# SCH_Flight-Computer_2024-07-14.net
KiCad netlist of a schematic drawn in EasyEDA
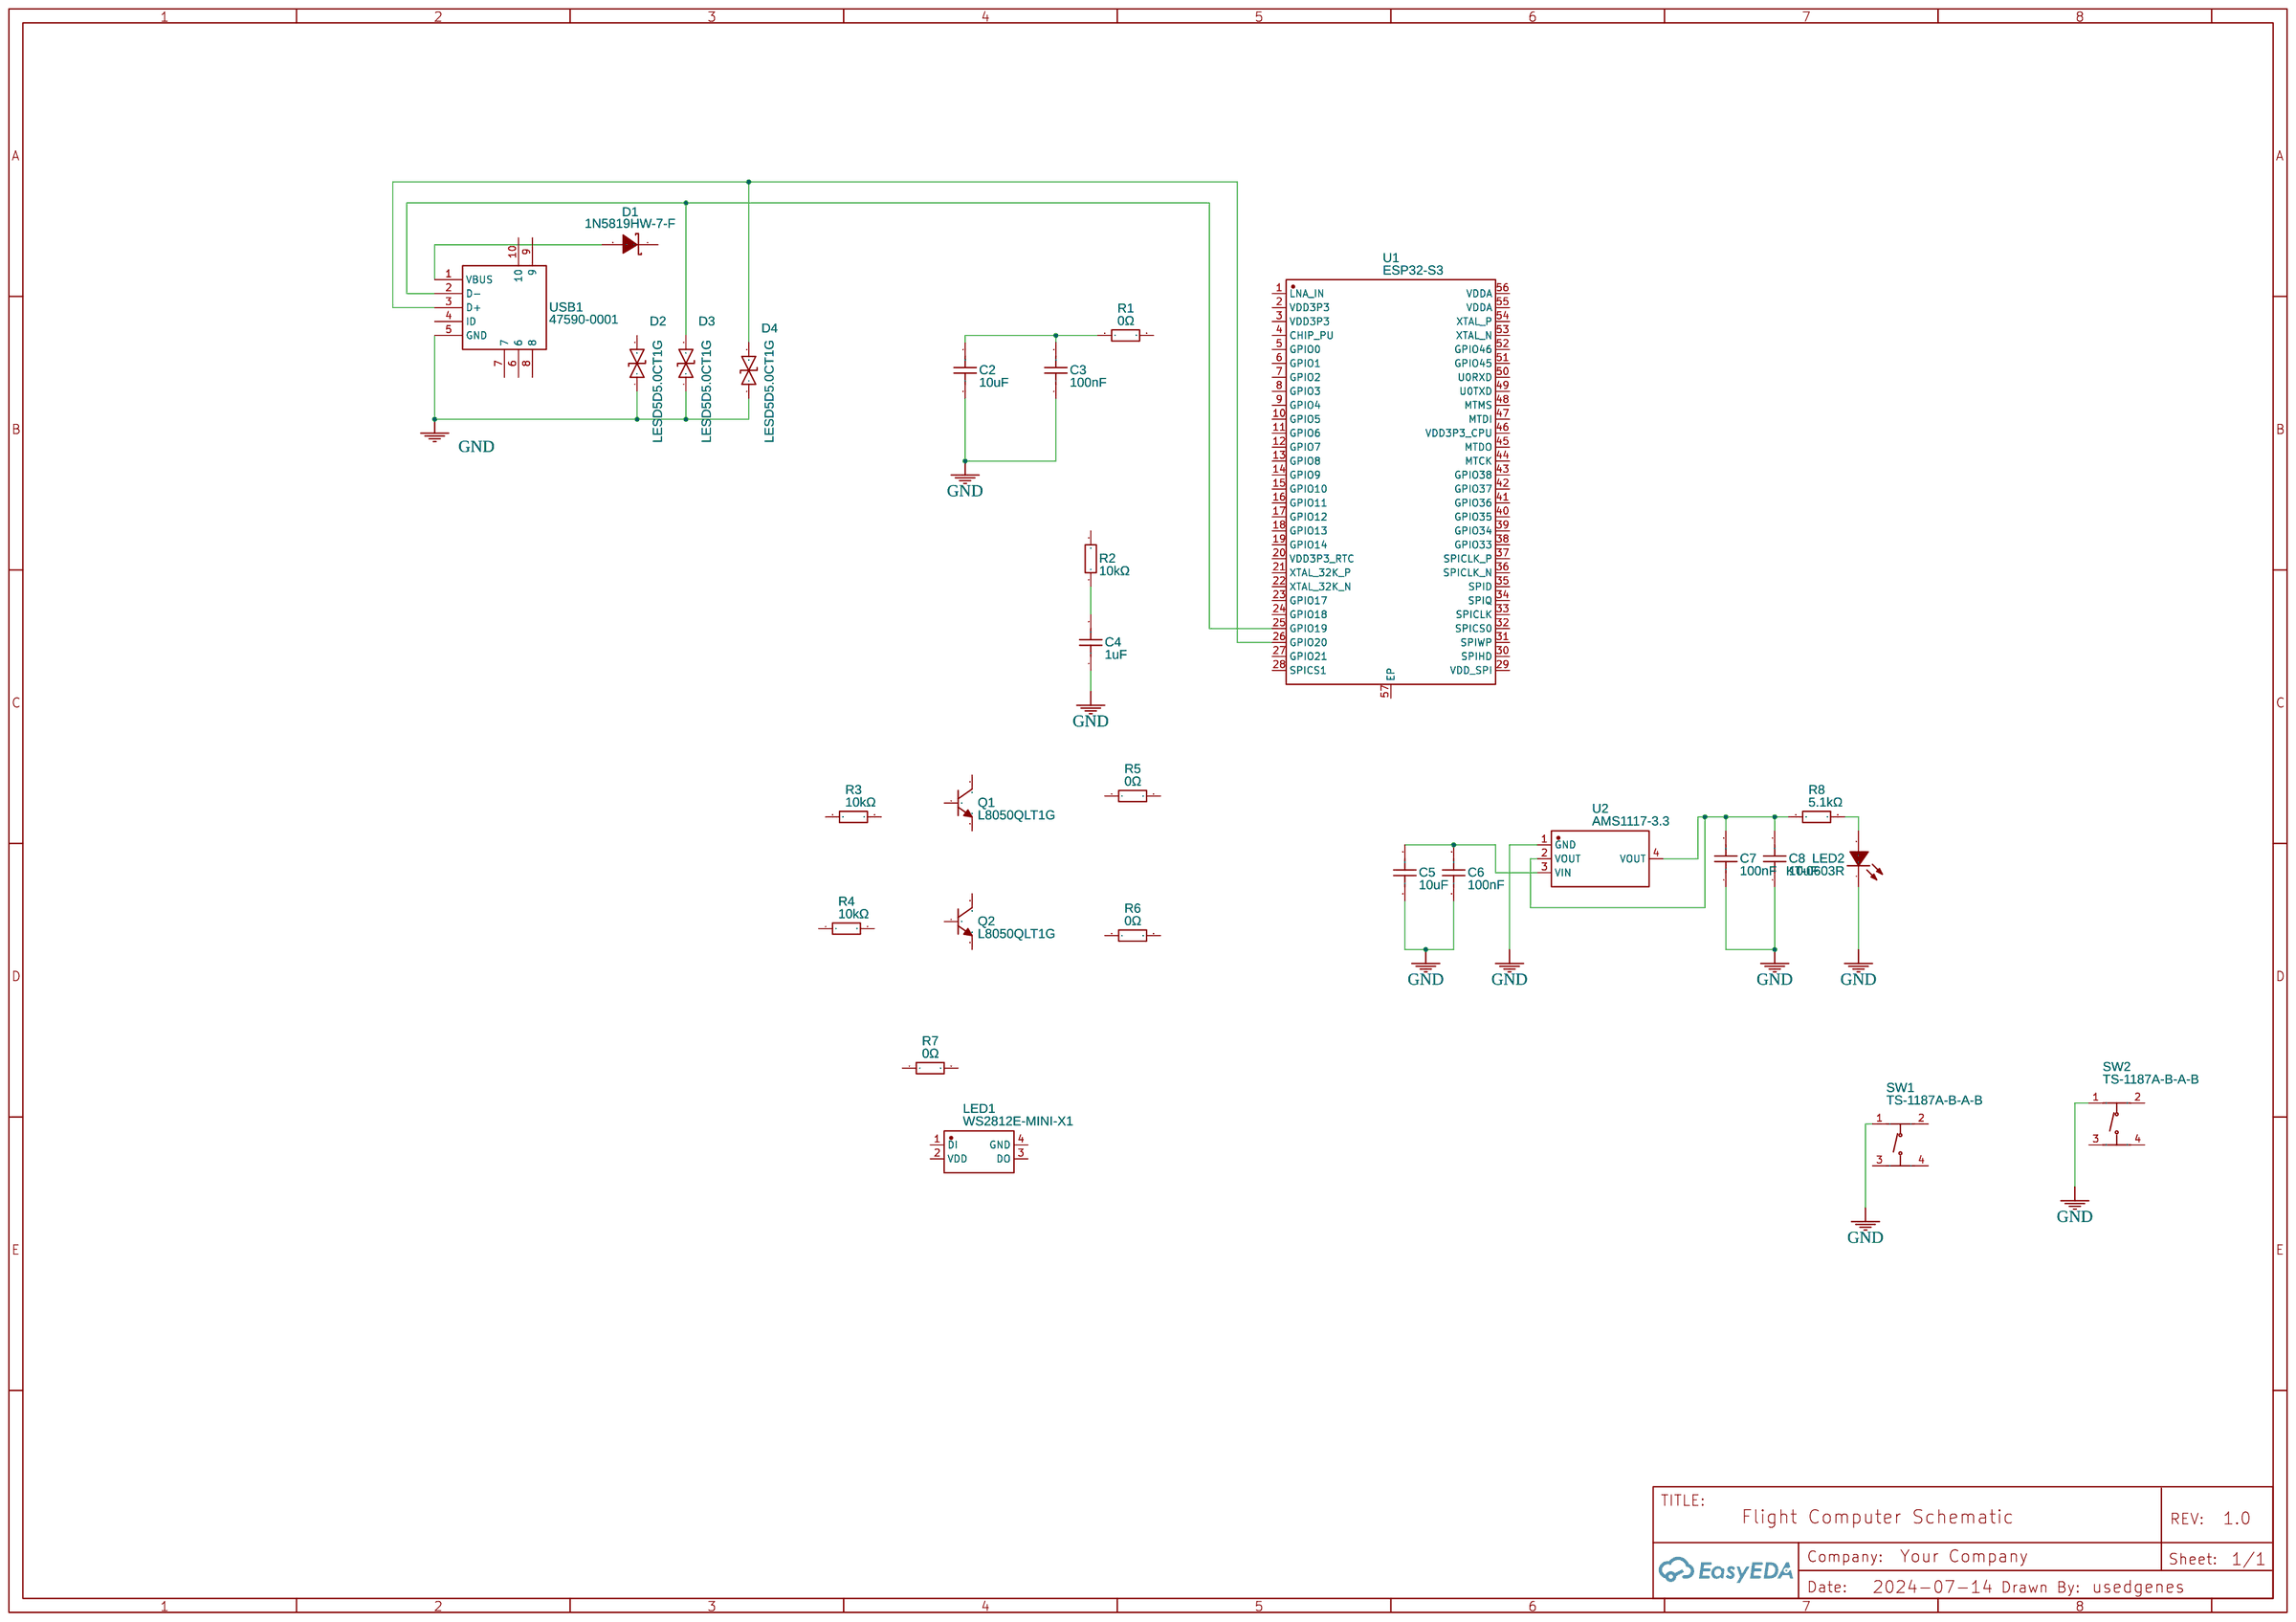
[diagram p0: schematic sheet]

(export (version "E")
  (design (tool "Eeschema 10.0.6"))
  (components
    (comp (ref "C2")
      (value "10uF")
      (fields
        (field (name "Manufacturer Part") "CL10A106KP8NNNC")
        (field (name "Manufacturer") "SAMSUNG(三星)")
      )
      (libsource (lib "") (part "CL10A106KP8NNNC"))
    )
    (comp (ref "C3")
      (value "100nF")
      (fields
        (field (name "Manufacturer Part") "CC0603KRX7R9BB104")
        (field (name "Manufacturer") "YAGEO(国巨)")
      )
      (libsource (lib "") (part "CC0603KRX7R9BB104"))
    )
    (comp (ref "C4")
      (value "1uF")
      (fields
        (field (name "Manufacturer Part") "CL10A105KB8NNNC")
        (field (name "Manufacturer") "SAMSUNG(三星)")
      )
      (libsource (lib "") (part "CL10A105KB8NNNC"))
    )
    (comp (ref "C5")
      (value "10uF")
      (fields
        (field (name "Manufacturer Part") "CL10A106KP8NNNC")
        (field (name "Manufacturer") "SAMSUNG(三星)")
      )
      (libsource (lib "") (part "CL10A106KP8NNNC_1"))
    )
    (comp (ref "C6")
      (value "100nF")
      (fields
        (field (name "Manufacturer Part") "CC0603KRX7R9BB104")
        (field (name "Manufacturer") "YAGEO(国巨)")
      )
      (libsource (lib "") (part "CC0603KRX7R9BB104"))
    )
    (comp (ref "C7")
      (value "100nF")
      (fields
        (field (name "Manufacturer Part") "CC0603KRX7R9BB104")
        (field (name "Manufacturer") "YAGEO(国巨)")
      )
      (libsource (lib "") (part "CC0603KRX7R9BB104"))
    )
    (comp (ref "C8")
      (value "10uF")
      (fields
        (field (name "Manufacturer Part") "CL10A106KP8NNNC")
        (field (name "Manufacturer") "SAMSUNG(三星)")
      )
      (libsource (lib "") (part "CL10A106KP8NNNC_1"))
    )
    (comp (ref "D1")
      (value "1N5819HW-7-F")
      (fields (field (name "Manufacturer") "DIODES(美台)"))
      (libsource (lib "") (part "1N5819HW-7-F"))
    )
    (comp (ref "D2")
      (value "LESD5D5.0CT1G")
      (fields (field (name "Manufacturer") "LRC(乐山无线电)"))
      (libsource (lib "") (part "LESD5D5.0CT1G"))
    )
    (comp (ref "D3")
      (value "LESD5D5.0CT1G")
      (fields (field (name "Manufacturer") "LRC(乐山无线电)"))
      (libsource (lib "") (part "LESD5D5.0CT1G"))
    )
    (comp (ref "D4")
      (value "LESD5D5.0CT1G")
      (fields (field (name "Manufacturer") "LRC(乐山无线电)"))
      (libsource (lib "") (part "LESD5D5.0CT1G"))
    )
    (comp (ref "LED1")
      (value "WS2812E-MINI-X1")
      (fields (field (name "Manufacturer") "worldsemi"))
      (libsource (lib "") (part "WS2812E-MINI-X1"))
    )
    (comp (ref "LED2")
      (value "KT-0603R")
      (fields (field (name "Manufacturer") "KENTO"))
      (libsource (lib "") (part "KT-0603R"))
    )
    (comp (ref "Q1")
      (value "L8050QLT1G")
      (fields (field (name "Manufacturer") "LRC(乐山无线电)"))
      (libsource (lib "") (part "L8050QLT1G"))
    )
    (comp (ref "Q2")
      (value "L8050QLT1G")
      (fields (field (name "Manufacturer") "LRC(乐山无线电)"))
      (libsource (lib "") (part "L8050QLT1G"))
    )
    (comp (ref "R1")
      (value "0Ω")
      (fields
        (field (name "Manufacturer Part") "0402WGF0000TCE")
        (field (name "Manufacturer") "UNI-ROYAL(厚声)")
      )
      (libsource (lib "") (part "0402WGF0000TCE"))
    )
    (comp (ref "R2")
      (value "10kΩ")
      (fields
        (field (name "Manufacturer Part") "0603WAF1002T5E")
        (field (name "Manufacturer") "UNI-ROYAL(厚声)")
      )
      (libsource (lib "") (part "0603WAF1002T5E_1"))
    )
    (comp (ref "R3")
      (value "10kΩ")
      (fields
        (field (name "Manufacturer Part") "0603WAF1002T5E")
        (field (name "Manufacturer") "UNI-ROYAL(厚声)")
      )
      (libsource (lib "") (part "0603WAF1002T5E"))
    )
    (comp (ref "R4")
      (value "10kΩ")
      (fields
        (field (name "Manufacturer Part") "0603WAF1002T5E")
        (field (name "Manufacturer") "UNI-ROYAL(厚声)")
      )
      (libsource (lib "") (part "0603WAF1002T5E"))
    )
    (comp (ref "R5")
      (value "0Ω")
      (fields
        (field (name "Manufacturer Part") "0402WGF0000TCE")
        (field (name "Manufacturer") "UNI-ROYAL(厚声)")
      )
      (libsource (lib "") (part "0402WGF0000TCE"))
    )
    (comp (ref "R6")
      (value "0Ω")
      (fields
        (field (name "Manufacturer Part") "0402WGF0000TCE")
        (field (name "Manufacturer") "UNI-ROYAL(厚声)")
      )
      (libsource (lib "") (part "0402WGF0000TCE"))
    )
    (comp (ref "R7")
      (value "0Ω")
      (fields
        (field (name "Manufacturer Part") "0402WGF0000TCE")
        (field (name "Manufacturer") "UNI-ROYAL(厚声)")
      )
      (libsource (lib "") (part "0402WGF0000TCE"))
    )
    (comp (ref "R8")
      (value "5.1kΩ")
      (fields
        (field (name "Manufacturer Part") "0603WAF5101T5E")
        (field (name "Manufacturer") "UNI-ROYAL(厚声)")
      )
      (libsource (lib "") (part "0603WAF5101T5E"))
    )
    (comp (ref "SW1")
      (value "TS-1187A-B-A-B")
      (fields (field (name "Manufacturer") "XKB Connectivity(中国星坤)"))
      (libsource (lib "") (part "TS-1187A-B-A-B"))
    )
    (comp (ref "SW2")
      (value "TS-1187A-B-A-B")
      (fields (field (name "Manufacturer") "XKB Connectivity(中国星坤)"))
      (libsource (lib "") (part "TS-1187A-B-A-B"))
    )
    (comp (ref "U1")
      (value "ESP32-S3")
      (fields (field (name "Manufacturer") "ESPRESSIF(乐鑫)"))
      (libsource (lib "") (part "ESP32-S3"))
    )
    (comp (ref "U2")
      (value "AMS1117-3.3")
      (fields (field (name "Manufacturer") "AMS"))
      (libsource (lib "") (part "AMS1117-3.3"))
    )
    (comp (ref "USB1")
      (value "47590-0001")
      (fields (field (name "Manufacturer Part") "475900001") (field (name "Manufacturer") "MOLEX"))
      (libsource (lib "") (part "47590-0001"))
    )
  )
  (nets
    (net (code "1") (name "GND") (class "Default")
      (node (ref "C2") (pin "2") (pinfunction "2_2") (pintype "unspecified"))
      (node (ref "C3") (pin "1") (pinfunction "1_1") (pintype "unspecified"))
      (node (ref "C4") (pin "1") (pinfunction "1_1") (pintype "unspecified"))
      (node (ref "C5") (pin "1") (pinfunction "1_1") (pintype "unspecified"))
      (node (ref "C6") (pin "1") (pinfunction "1_1") (pintype "unspecified"))
      (node (ref "C7") (pin "1") (pinfunction "1_1") (pintype "unspecified"))
      (node (ref "C8") (pin "1") (pinfunction "1_1") (pintype "unspecified"))
      (node (ref "D2") (pin "1") (pinfunction "1_1") (pintype "unspecified"))
      (node (ref "D3") (pin "1") (pinfunction "1_1") (pintype "unspecified"))
      (node (ref "D4") (pin "1") (pinfunction "1_1") (pintype "unspecified"))
      (node (ref "LED2") (pin "1") (pinfunction "K_1") (pintype "unspecified"))
      (node (ref "SW1") (pin "1") (pinfunction "A_1") (pintype "unspecified"))
      (node (ref "SW2") (pin "1") (pinfunction "A_1") (pintype "unspecified"))
      (node (ref "U2") (pin "1") (pinfunction "GND_1") (pintype "unspecified"))
      (node (ref "USB1") (pin "5") (pinfunction "GND_5") (pintype "unspecified"))
    )
    (net (code "2") (name "Net-(C2-Pad1)") (class "Default")
      (node (ref "C2") (pin "1") (pinfunction "1_1") (pintype "unspecified"))
      (node (ref "C3") (pin "2") (pinfunction "2_2") (pintype "unspecified"))
      (node (ref "R1") (pin "1") (pinfunction "1_1") (pintype "input"))
    )
    (net (code "3") (name "Net-(C4-Pad2)") (class "Default")
      (node (ref "C4") (pin "2") (pinfunction "2_2") (pintype "unspecified"))
      (node (ref "R2") (pin "1") (pinfunction "1_1") (pintype "input"))
    )
    (net (code "4") (name "Net-(C7-Pad2)") (class "Default")
      (node (ref "C7") (pin "2") (pinfunction "2_2") (pintype "unspecified"))
      (node (ref "C8") (pin "2") (pinfunction "2_2") (pintype "unspecified"))
      (node (ref "R8") (pin "1") (pinfunction "1_1") (pintype "input"))
      (node (ref "U2") (pin "2") (pinfunction "VOUT_2") (pintype "unspecified"))
      (node (ref "U2") (pin "4") (pinfunction "VOUT_4") (pintype "unspecified"))
    )
    (net (code "5") (name "Net-(D1-A)") (class "Default")
      (node (ref "D1") (pin "2") (pinfunction "A_2") (pintype "unspecified"))
      (node (ref "USB1") (pin "1") (pinfunction "VBUS_1") (pintype "unspecified"))
    )
    (net (code "6") (name "Net-(LED2-A)") (class "Default")
      (node (ref "LED2") (pin "2") (pinfunction "A_2") (pintype "unspecified"))
      (node (ref "R8") (pin "2") (pinfunction "2_2") (pintype "input"))
    )
    (net (code "7") (name "Net-(U1-GPIO19)") (class "Default")
      (node (ref "D3") (pin "2") (pinfunction "2_2") (pintype "unspecified"))
      (node (ref "U1") (pin "25") (pinfunction "GPIO19_25") (pintype "unspecified"))
      (node (ref "USB1") (pin "2") (pinfunction "D-_2") (pintype "unspecified"))
    )
    (net (code "8") (name "Net-(U1-GPIO20)") (class "Default")
      (node (ref "D4") (pin "2") (pinfunction "2_2") (pintype "unspecified"))
      (node (ref "U1") (pin "26") (pinfunction "GPIO20_26") (pintype "unspecified"))
      (node (ref "USB1") (pin "3") (pinfunction "D+_3") (pintype "unspecified"))
    )
    (net (code "9") (name "Net-(U2-VIN)") (class "Default")
      (node (ref "C5") (pin "2") (pinfunction "2_2") (pintype "unspecified"))
      (node (ref "C6") (pin "2") (pinfunction "2_2") (pintype "unspecified"))
      (node (ref "U2") (pin "3") (pinfunction "VIN_3") (pintype "unspecified"))
    )
    (net (code "10") (name "unconnected-(D1-K-Pad1)") (class "Default")
      (node (ref "D1") (pin "1") (pinfunction "K_1") (pintype "unspecified"))
    )
    (net (code "11") (name "unconnected-(D2-Pad2)") (class "Default")
      (node (ref "D2") (pin "2") (pinfunction "2_2") (pintype "unspecified"))
    )
    (net (code "12") (name "unconnected-(LED1-DI-Pad1)") (class "Default")
      (node (ref "LED1") (pin "1") (pinfunction "DI_1") (pintype "unspecified"))
    )
    (net (code "13") (name "unconnected-(LED1-DO-Pad3)") (class "Default")
      (node (ref "LED1") (pin "3") (pinfunction "DO_3") (pintype "unspecified"))
    )
    (net (code "14") (name "unconnected-(LED1-GND-Pad4)") (class "Default")
      (node (ref "LED1") (pin "4") (pinfunction "GND_4") (pintype "unspecified"))
    )
    (net (code "15") (name "unconnected-(LED1-VDD-Pad2)") (class "Default")
      (node (ref "LED1") (pin "2") (pinfunction "VDD_2") (pintype "unspecified"))
    )
    (net (code "16") (name "unconnected-(Q1-B-Pad1)") (class "Default")
      (node (ref "Q1") (pin "1") (pinfunction "B_1") (pintype "unspecified"))
    )
    (net (code "17") (name "unconnected-(Q1-C-Pad3)") (class "Default")
      (node (ref "Q1") (pin "3") (pinfunction "C_3") (pintype "unspecified"))
    )
    (net (code "18") (name "unconnected-(Q1-E-Pad2)") (class "Default")
      (node (ref "Q1") (pin "2") (pinfunction "E_2") (pintype "unspecified"))
    )
    (net (code "19") (name "unconnected-(Q2-B-Pad1)") (class "Default")
      (node (ref "Q2") (pin "1") (pinfunction "B_1") (pintype "unspecified"))
    )
    (net (code "20") (name "unconnected-(Q2-C-Pad3)") (class "Default")
      (node (ref "Q2") (pin "3") (pinfunction "C_3") (pintype "unspecified"))
    )
    (net (code "21") (name "unconnected-(Q2-E-Pad2)") (class "Default")
      (node (ref "Q2") (pin "2") (pinfunction "E_2") (pintype "unspecified"))
    )
    (net (code "22") (name "unconnected-(R1-Pad2)") (class "Default")
      (node (ref "R1") (pin "2") (pinfunction "2_2") (pintype "input"))
    )
    (net (code "23") (name "unconnected-(R2-Pad2)") (class "Default")
      (node (ref "R2") (pin "2") (pinfunction "2_2") (pintype "input"))
    )
    (net (code "24") (name "unconnected-(R3-Pad1)") (class "Default")
      (node (ref "R3") (pin "1") (pinfunction "1_1") (pintype "input"))
    )
    (net (code "25") (name "unconnected-(R3-Pad2)") (class "Default")
      (node (ref "R3") (pin "2") (pinfunction "2_2") (pintype "input"))
    )
    (net (code "26") (name "unconnected-(R4-Pad1)") (class "Default")
      (node (ref "R4") (pin "1") (pinfunction "1_1") (pintype "input"))
    )
    (net (code "27") (name "unconnected-(R4-Pad2)") (class "Default")
      (node (ref "R4") (pin "2") (pinfunction "2_2") (pintype "input"))
    )
    (net (code "28") (name "unconnected-(R5-Pad1)") (class "Default")
      (node (ref "R5") (pin "1") (pinfunction "1_1") (pintype "input"))
    )
    (net (code "29") (name "unconnected-(R5-Pad2)") (class "Default")
      (node (ref "R5") (pin "2") (pinfunction "2_2") (pintype "input"))
    )
    (net (code "30") (name "unconnected-(R6-Pad1)") (class "Default")
      (node (ref "R6") (pin "1") (pinfunction "1_1") (pintype "input"))
    )
    (net (code "31") (name "unconnected-(R6-Pad2)") (class "Default")
      (node (ref "R6") (pin "2") (pinfunction "2_2") (pintype "input"))
    )
    (net (code "32") (name "unconnected-(R7-Pad1)") (class "Default")
      (node (ref "R7") (pin "1") (pinfunction "1_1") (pintype "input"))
    )
    (net (code "33") (name "unconnected-(R7-Pad2)") (class "Default")
      (node (ref "R7") (pin "2") (pinfunction "2_2") (pintype "input"))
    )
    (net (code "34") (name "unconnected-(SW1-B-Pad2)") (class "Default")
      (node (ref "SW1") (pin "2") (pinfunction "B_2") (pintype "unspecified"))
    )
    (net (code "35") (name "unconnected-(SW1-C-Pad3)") (class "Default")
      (node (ref "SW1") (pin "3") (pinfunction "C_3") (pintype "unspecified"))
    )
    (net (code "36") (name "unconnected-(SW1-D-Pad4)") (class "Default")
      (node (ref "SW1") (pin "4") (pinfunction "D_4") (pintype "unspecified"))
    )
    (net (code "37") (name "unconnected-(SW2-B-Pad2)") (class "Default")
      (node (ref "SW2") (pin "2") (pinfunction "B_2") (pintype "unspecified"))
    )
    (net (code "38") (name "unconnected-(SW2-C-Pad3)") (class "Default")
      (node (ref "SW2") (pin "3") (pinfunction "C_3") (pintype "unspecified"))
    )
    (net (code "39") (name "unconnected-(SW2-D-Pad4)") (class "Default")
      (node (ref "SW2") (pin "4") (pinfunction "D_4") (pintype "unspecified"))
    )
    (net (code "40") (name "unconnected-(U1-CHIP_PU-Pad4)") (class "Default")
      (node (ref "U1") (pin "4") (pinfunction "CHIP_PU_4") (pintype "unspecified"))
    )
    (net (code "41") (name "unconnected-(U1-EP-Pad57)") (class "Default")
      (node (ref "U1") (pin "57") (pinfunction "EP_57") (pintype "unspecified"))
    )
    (net (code "42") (name "unconnected-(U1-GPIO0-Pad5)") (class "Default")
      (node (ref "U1") (pin "5") (pinfunction "GPIO0_5") (pintype "unspecified"))
    )
    (net (code "43") (name "unconnected-(U1-GPIO1-Pad6)") (class "Default")
      (node (ref "U1") (pin "6") (pinfunction "GPIO1_6") (pintype "unspecified"))
    )
    (net (code "44") (name "unconnected-(U1-GPIO2-Pad7)") (class "Default")
      (node (ref "U1") (pin "7") (pinfunction "GPIO2_7") (pintype "unspecified"))
    )
    (net (code "45") (name "unconnected-(U1-GPIO3-Pad8)") (class "Default")
      (node (ref "U1") (pin "8") (pinfunction "GPIO3_8") (pintype "unspecified"))
    )
    (net (code "46") (name "unconnected-(U1-GPIO4-Pad9)") (class "Default")
      (node (ref "U1") (pin "9") (pinfunction "GPIO4_9") (pintype "unspecified"))
    )
    (net (code "47") (name "unconnected-(U1-GPIO5-Pad10)") (class "Default")
      (node (ref "U1") (pin "10") (pinfunction "GPIO5_10") (pintype "unspecified"))
    )
    (net (code "48") (name "unconnected-(U1-GPIO6-Pad11)") (class "Default")
      (node (ref "U1") (pin "11") (pinfunction "GPIO6_11") (pintype "unspecified"))
    )
    (net (code "49") (name "unconnected-(U1-GPIO7-Pad12)") (class "Default")
      (node (ref "U1") (pin "12") (pinfunction "GPIO7_12") (pintype "unspecified"))
    )
    (net (code "50") (name "unconnected-(U1-GPIO8-Pad13)") (class "Default")
      (node (ref "U1") (pin "13") (pinfunction "GPIO8_13") (pintype "unspecified"))
    )
    (net (code "51") (name "unconnected-(U1-GPIO9-Pad14)") (class "Default")
      (node (ref "U1") (pin "14") (pinfunction "GPIO9_14") (pintype "unspecified"))
    )
    (net (code "52") (name "unconnected-(U1-GPIO10-Pad15)") (class "Default")
      (node (ref "U1") (pin "15") (pinfunction "GPIO10_15") (pintype "unspecified"))
    )
    (net (code "53") (name "unconnected-(U1-GPIO11-Pad16)") (class "Default")
      (node (ref "U1") (pin "16") (pinfunction "GPIO11_16") (pintype "unspecified"))
    )
    (net (code "54") (name "unconnected-(U1-GPIO12-Pad17)") (class "Default")
      (node (ref "U1") (pin "17") (pinfunction "GPIO12_17") (pintype "unspecified"))
    )
    (net (code "55") (name "unconnected-(U1-GPIO13-Pad18)") (class "Default")
      (node (ref "U1") (pin "18") (pinfunction "GPIO13_18") (pintype "unspecified"))
    )
    (net (code "56") (name "unconnected-(U1-GPIO14-Pad19)") (class "Default")
      (node (ref "U1") (pin "19") (pinfunction "GPIO14_19") (pintype "unspecified"))
    )
    (net (code "57") (name "unconnected-(U1-GPIO17-Pad23)") (class "Default")
      (node (ref "U1") (pin "23") (pinfunction "GPIO17_23") (pintype "unspecified"))
    )
    (net (code "58") (name "unconnected-(U1-GPIO18-Pad24)") (class "Default")
      (node (ref "U1") (pin "24") (pinfunction "GPIO18_24") (pintype "unspecified"))
    )
    (net (code "59") (name "unconnected-(U1-GPIO21-Pad27)") (class "Default")
      (node (ref "U1") (pin "27") (pinfunction "GPIO21_27") (pintype "unspecified"))
    )
    (net (code "60") (name "unconnected-(U1-GPIO33-Pad38)") (class "Default")
      (node (ref "U1") (pin "38") (pinfunction "GPIO33_38") (pintype "unspecified"))
    )
    (net (code "61") (name "unconnected-(U1-GPIO34-Pad39)") (class "Default")
      (node (ref "U1") (pin "39") (pinfunction "GPIO34_39") (pintype "unspecified"))
    )
    (net (code "62") (name "unconnected-(U1-GPIO35-Pad40)") (class "Default")
      (node (ref "U1") (pin "40") (pinfunction "GPIO35_40") (pintype "unspecified"))
    )
    (net (code "63") (name "unconnected-(U1-GPIO36-Pad41)") (class "Default")
      (node (ref "U1") (pin "41") (pinfunction "GPIO36_41") (pintype "unspecified"))
    )
    (net (code "64") (name "unconnected-(U1-GPIO37-Pad42)") (class "Default")
      (node (ref "U1") (pin "42") (pinfunction "GPIO37_42") (pintype "unspecified"))
    )
    (net (code "65") (name "unconnected-(U1-GPIO38-Pad43)") (class "Default")
      (node (ref "U1") (pin "43") (pinfunction "GPIO38_43") (pintype "unspecified"))
    )
    (net (code "66") (name "unconnected-(U1-GPIO45-Pad51)") (class "Default")
      (node (ref "U1") (pin "51") (pinfunction "GPIO45_51") (pintype "unspecified"))
    )
    (net (code "67") (name "unconnected-(U1-GPIO46-Pad52)") (class "Default")
      (node (ref "U1") (pin "52") (pinfunction "GPIO46_52") (pintype "unspecified"))
    )
    (net (code "68") (name "unconnected-(U1-LNA_IN-Pad1)") (class "Default")
      (node (ref "U1") (pin "1") (pinfunction "LNA_IN_1") (pintype "unspecified"))
    )
    (net (code "69") (name "unconnected-(U1-MTCK-Pad44)") (class "Default")
      (node (ref "U1") (pin "44") (pinfunction "MTCK_44") (pintype "unspecified"))
    )
    (net (code "70") (name "unconnected-(U1-MTDI-Pad47)") (class "Default")
      (node (ref "U1") (pin "47") (pinfunction "MTDI_47") (pintype "unspecified"))
    )
    (net (code "71") (name "unconnected-(U1-MTDO-Pad45)") (class "Default")
      (node (ref "U1") (pin "45") (pinfunction "MTDO_45") (pintype "unspecified"))
    )
    (net (code "72") (name "unconnected-(U1-MTMS-Pad48)") (class "Default")
      (node (ref "U1") (pin "48") (pinfunction "MTMS_48") (pintype "unspecified"))
    )
    (net (code "73") (name "unconnected-(U1-SPICLK-Pad33)") (class "Default")
      (node (ref "U1") (pin "33") (pinfunction "SPICLK_33") (pintype "unspecified"))
    )
    (net (code "74") (name "unconnected-(U1-SPICLK_N-Pad36)") (class "Default")
      (node (ref "U1") (pin "36") (pinfunction "SPICLK_N_36") (pintype "unspecified"))
    )
    (net (code "75") (name "unconnected-(U1-SPICLK_P-Pad37)") (class "Default")
      (node (ref "U1") (pin "37") (pinfunction "SPICLK_P_37") (pintype "unspecified"))
    )
    (net (code "76") (name "unconnected-(U1-SPICS0-Pad32)") (class "Default")
      (node (ref "U1") (pin "32") (pinfunction "SPICS0_32") (pintype "unspecified"))
    )
    (net (code "77") (name "unconnected-(U1-SPICS1-Pad28)") (class "Default")
      (node (ref "U1") (pin "28") (pinfunction "SPICS1_28") (pintype "unspecified"))
    )
    (net (code "78") (name "unconnected-(U1-SPID-Pad35)") (class "Default")
      (node (ref "U1") (pin "35") (pinfunction "SPID_35") (pintype "unspecified"))
    )
    (net (code "79") (name "unconnected-(U1-SPIHD-Pad30)") (class "Default")
      (node (ref "U1") (pin "30") (pinfunction "SPIHD_30") (pintype "unspecified"))
    )
    (net (code "80") (name "unconnected-(U1-SPIQ-Pad34)") (class "Default")
      (node (ref "U1") (pin "34") (pinfunction "SPIQ_34") (pintype "unspecified"))
    )
    (net (code "81") (name "unconnected-(U1-SPIWP-Pad31)") (class "Default")
      (node (ref "U1") (pin "31") (pinfunction "SPIWP_31") (pintype "unspecified"))
    )
    (net (code "82") (name "unconnected-(U1-U0RXD-Pad50)") (class "Default")
      (node (ref "U1") (pin "50") (pinfunction "U0RXD_50") (pintype "unspecified"))
    )
    (net (code "83") (name "unconnected-(U1-U0TXD-Pad49)") (class "Default")
      (node (ref "U1") (pin "49") (pinfunction "U0TXD_49") (pintype "unspecified"))
    )
    (net (code "84") (name "unconnected-(U1-VDD3P3-Pad2)") (class "Default")
      (node (ref "U1") (pin "2") (pinfunction "VDD3P3_2") (pintype "unspecified"))
    )
    (net (code "85") (name "unconnected-(U1-VDD3P3-Pad3)") (class "Default")
      (node (ref "U1") (pin "3") (pinfunction "VDD3P3_3") (pintype "unspecified"))
    )
    (net (code "86") (name "unconnected-(U1-VDD3P3_CPU-Pad46)") (class "Default")
      (node (ref "U1") (pin "46") (pinfunction "VDD3P3_CPU_46") (pintype "unspecified"))
    )
    (net (code "87") (name "unconnected-(U1-VDD3P3_RTC-Pad20)") (class "Default")
      (node (ref "U1") (pin "20") (pinfunction "VDD3P3_RTC_20") (pintype "unspecified"))
    )
    (net (code "88") (name "unconnected-(U1-VDDA-Pad55)") (class "Default")
      (node (ref "U1") (pin "55") (pinfunction "VDDA_55") (pintype "unspecified"))
    )
    (net (code "89") (name "unconnected-(U1-VDDA-Pad56)") (class "Default")
      (node (ref "U1") (pin "56") (pinfunction "VDDA_56") (pintype "unspecified"))
    )
    (net (code "90") (name "unconnected-(U1-VDD_SPI-Pad29)") (class "Default")
      (node (ref "U1") (pin "29") (pinfunction "VDD_SPI_29") (pintype "unspecified"))
    )
    (net (code "91") (name "unconnected-(U1-XTAL_32K_N-Pad22)") (class "Default")
      (node (ref "U1") (pin "22") (pinfunction "XTAL_32K_N_22") (pintype "unspecified"))
    )
    (net (code "92") (name "unconnected-(U1-XTAL_32K_P-Pad21)") (class "Default")
      (node (ref "U1") (pin "21") (pinfunction "XTAL_32K_P_21") (pintype "unspecified"))
    )
    (net (code "93") (name "unconnected-(U1-XTAL_N-Pad53)") (class "Default")
      (node (ref "U1") (pin "53") (pinfunction "XTAL_N_53") (pintype "unspecified"))
    )
    (net (code "94") (name "unconnected-(U1-XTAL_P-Pad54)") (class "Default")
      (node (ref "U1") (pin "54") (pinfunction "XTAL_P_54") (pintype "unspecified"))
    )
    (net (code "95") (name "unconnected-(USB1-ID-Pad4)") (class "Default")
      (node (ref "USB1") (pin "4") (pinfunction "ID_4") (pintype "unspecified"))
    )
    (net (code "96") (name "unconnected-(USB1-Pad6)") (class "Default")
      (node (ref "USB1") (pin "6") (pinfunction "6_6") (pintype "unspecified"))
    )
    (net (code "97") (name "unconnected-(USB1-Pad7)") (class "Default")
      (node (ref "USB1") (pin "7") (pinfunction "7_7") (pintype "unspecified"))
    )
    (net (code "98") (name "unconnected-(USB1-Pad8)") (class "Default")
      (node (ref "USB1") (pin "8") (pinfunction "8_8") (pintype "unspecified"))
    )
    (net (code "99") (name "unconnected-(USB1-Pad9)") (class "Default")
      (node (ref "USB1") (pin "9") (pinfunction "9_9") (pintype "unspecified"))
    )
    (net (code "100") (name "unconnected-(USB1-Pad10)") (class "Default")
      (node (ref "USB1") (pin "10") (pinfunction "10_10") (pintype "unspecified"))
    )
  )
)
